# EPS_CTRL_AB_Supply.net
KiCad netlist of a schematic drawn in Altium Designer
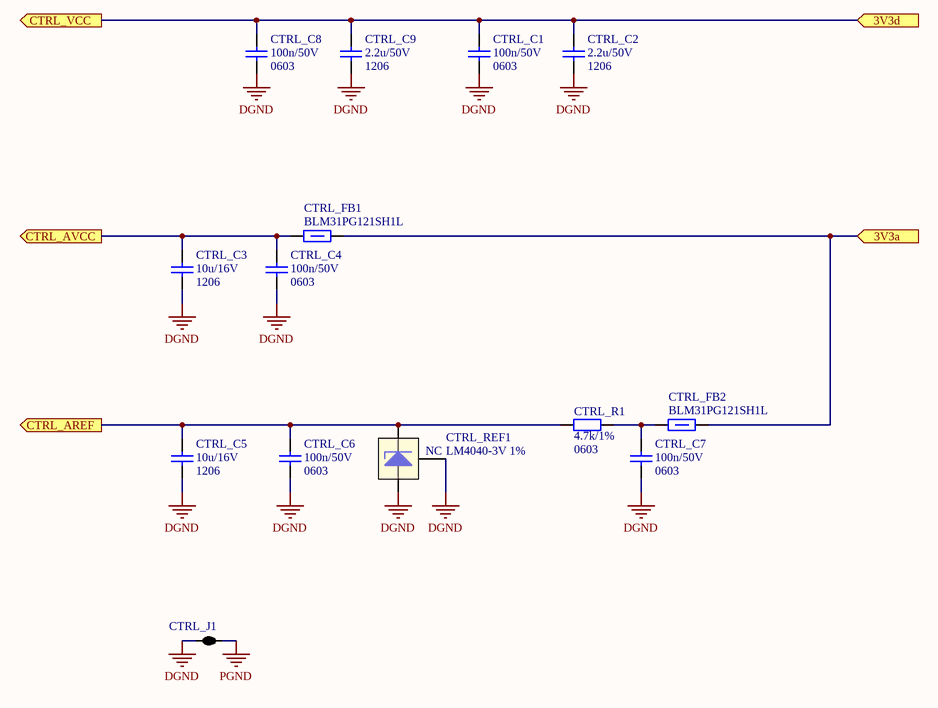
[diagram p0: EPS_CTRL_AB_Supply.SchDoc]

(export (version "E")
  (design (tool "Eeschema 10.0.6"))
  (components
    (comp (ref "CTRL_C1")
      (value "100n/50V")
      (footprint "SMD_Capacitor_0603")
      (description "Ceramic Cap Kemet COTS 100n/50V X7R 0603")
      (fields
        (field (name "MANUFACTURER") "Kemet")
        (field (name "MANUFACTURERPARTNUMBER") "C0603T104K5RALTU")
        (field (name "PACKAGE") "0603")
      )
      (libsource (lib "capacitors") (part "Cer_C0603T104K5RALTU"))
    )
    (comp (ref "CTRL_C2")
      (value "2.2u/50V")
      (footprint "SMD_Capacitor_1206")
      (description "Ceramic Cap Murata Automotive 2.2u/50V X7R 1206")
      (fields
        (field (name "MANUFACTURER") "Murata")
        (field (name "MANUFACTURERPARTNUMBER") "GCJ31CR71H225KA12L")
        (field (name "PACKAGE") "1206")
      )
      (libsource (lib "capacitors") (part "Cer_GCJ31CR71H225KA12L"))
    )
    (comp (ref "CTRL_C3")
      (value "10u/16V")
      (footprint "SMD_Capacitor_1206")
      (description "Ceramic Cap Kemet COTS 10u/16V X7R 1206")
      (fields
        (field (name "MANUFACTURERPARTNUMBER") "C1206T106K4RACTU")
        (field (name "MANUFACTURER") "Kemet")
        (field (name "PACKGE") "1206")
      )
      (libsource (lib "capacitors") (part "Cer_C1206T106K4RACTU"))
    )
    (comp (ref "CTRL_C4")
      (value "100n/50V")
      (footprint "SMD_Capacitor_0603")
      (description "Ceramic Cap Kemet COTS 100n/50V X7R 0603")
      (fields
        (field (name "MANUFACTURER") "Kemet")
        (field (name "MANUFACTURERPARTNUMBER") "C0603T104K5RALTU")
        (field (name "PACKAGE") "0603")
      )
      (libsource (lib "capacitors") (part "Cer_C0603T104K5RALTU"))
    )
    (comp (ref "CTRL_C5")
      (value "10u/16V")
      (footprint "SMD_Capacitor_1206")
      (description "Ceramic Cap Kemet COTS 10u/16V X7R 1206")
      (fields
        (field (name "MANUFACTURERPARTNUMBER") "C1206T106K4RACTU")
        (field (name "MANUFACTURER") "Kemet")
        (field (name "PACKGE") "1206")
      )
      (libsource (lib "capacitors") (part "Cer_C1206T106K4RACTU"))
    )
    (comp (ref "CTRL_C6")
      (value "100n/50V")
      (footprint "SMD_Capacitor_0603")
      (description "Ceramic Cap Kemet COTS 100n/50V X7R 0603")
      (fields
        (field (name "MANUFACTURER") "Kemet")
        (field (name "MANUFACTURERPARTNUMBER") "C0603T104K5RALTU")
        (field (name "PACKAGE") "0603")
      )
      (libsource (lib "capacitors") (part "Cer_C0603T104K5RALTU"))
    )
    (comp (ref "CTRL_C7")
      (value "100n/50V")
      (footprint "SMD_Capacitor_0603")
      (description "Ceramic Cap Kemet COTS 100n/50V X7R 0603")
      (fields
        (field (name "MANUFACTURER") "Kemet")
        (field (name "MANUFACTURERPARTNUMBER") "C0603T104K5RALTU")
        (field (name "PACKAGE") "0603")
      )
      (libsource (lib "capacitors") (part "Cer_C0603T104K5RALTU"))
    )
    (comp (ref "CTRL_C8")
      (value "100n/50V")
      (footprint "SMD_Capacitor_0603")
      (description "Ceramic Cap Kemet COTS 100n/50V X7R 0603")
      (fields
        (field (name "MANUFACTURER") "Kemet")
        (field (name "MANUFACTURERPARTNUMBER") "C0603T104K5RALTU")
        (field (name "PACKAGE") "0603")
      )
      (libsource (lib "capacitors") (part "Cer_C0603T104K5RALTU"))
    )
    (comp (ref "CTRL_C9")
      (value "2.2u/50V")
      (footprint "SMD_Capacitor_1206")
      (description "Ceramic Cap Murata Automotive 2.2u/50V X7R 1206")
      (fields
        (field (name "MANUFACTURER") "Murata")
        (field (name "MANUFACTURERPARTNUMBER") "GCJ31CR71H225KA12L")
        (field (name "PACKAGE") "1206")
      )
      (libsource (lib "capacitors") (part "Cer_GCJ31CR71H225KA12L"))
    )
    (comp (ref "CTRL_FB1")
      (value "120R/100MHz")
      (footprint "SMD_FerriteBead_1206")
      (description "Ferrite bead, 1206, 0.02HM, 3.5A.")
      (fields (field (name "MANUFACTURER") "Murata") (field (name "MANUFACTURERPARTNUMBER") "BLM31PG121SH1L"))
      (libsource (lib "inductors") (part "BLM31PG121SH1L"))
    )
    (comp (ref "CTRL_FB2")
      (value "120R/100MHz")
      (footprint "SMD_FerriteBead_1206")
      (description "Ferrite bead, 1206, 0.02HM, 3.5A.")
      (fields (field (name "MANUFACTURER") "Murata") (field (name "MANUFACTURERPARTNUMBER") "BLM31PG121SH1L"))
      (libsource (lib "inductors") (part "BLM31PG121SH1L"))
    )
    (comp (ref "CTRL_J1")
      (value "2 way net tie junction")
      (footprint "2way_LP")
      (libsource (lib "NetTieLib") (part "2way"))
    )
    (comp (ref "CTRL_R1")
      (value "4.7k/1%")
      (footprint "SMD_Resistor_0603")
      (fields (field (name "PACKAGE") "0603"))
      (libsource (lib "resistors") (part "Res"))
    )
    (comp (ref "CTRL_REF1")
      (value "LM4040-3V 1%")
      (footprint "SOT23-3")
      (description "Shunt V-REF, 3V, 1%, SOT23-3")
      (fields
        (field (name "MANUFACTURERPARTNUMBER") "LM4040DIM3-3.0")
        (field (name "MANUFACTURER") "Texas Instruments")
      )
      (libsource (lib "diodes") (part "LM4040DIM3-3.0"))
    )
  )
  (nets
    (net (code "1") (name "/3V3a") (class "Default")
      (node (ref "CTRL_FB1") (pin "1") (pinfunction "1_1") (pintype "passive"))
      (node (ref "CTRL_FB2") (pin "1") (pinfunction "1_1") (pintype "passive"))
    )
    (net (code "2") (name "/3V3d") (class "Default")
      (node (ref "CTRL_C1") (pin "1") (pinfunction "1_1") (pintype "passive"))
      (node (ref "CTRL_C2") (pin "1") (pinfunction "1_1") (pintype "passive"))
      (node (ref "CTRL_C8") (pin "1") (pinfunction "1_1") (pintype "passive"))
      (node (ref "CTRL_C9") (pin "1") (pinfunction "1_1") (pintype "passive"))
    )
    (net (code "3") (name "/CTRL_AREF") (class "Default")
      (node (ref "CTRL_C5") (pin "1") (pinfunction "1_1") (pintype "passive"))
      (node (ref "CTRL_C6") (pin "1") (pinfunction "1_1") (pintype "passive"))
      (node (ref "CTRL_R1") (pin "1") (pinfunction "1_1") (pintype "passive"))
      (node (ref "CTRL_REF1") (pin "1") (pinfunction "K_1") (pintype "passive"))
    )
    (net (code "4") (name "/CTRL_AVCC") (class "Default")
      (node (ref "CTRL_C3") (pin "1") (pinfunction "1_1") (pintype "passive"))
      (node (ref "CTRL_C4") (pin "1") (pinfunction "1_1") (pintype "passive"))
      (node (ref "CTRL_FB1") (pin "2") (pinfunction "2_2") (pintype "passive"))
    )
    (net (code "5") (name "DGND") (class "Default")
      (node (ref "CTRL_C1") (pin "2") (pinfunction "2_2") (pintype "passive"))
      (node (ref "CTRL_C2") (pin "2") (pinfunction "2_2") (pintype "passive"))
      (node (ref "CTRL_C3") (pin "2") (pinfunction "2_2") (pintype "passive"))
      (node (ref "CTRL_C4") (pin "2") (pinfunction "2_2") (pintype "passive"))
      (node (ref "CTRL_C5") (pin "2") (pinfunction "2_2") (pintype "passive"))
      (node (ref "CTRL_C6") (pin "2") (pinfunction "2_2") (pintype "passive"))
      (node (ref "CTRL_C7") (pin "2") (pinfunction "2_2") (pintype "passive"))
      (node (ref "CTRL_C8") (pin "2") (pinfunction "2_2") (pintype "passive"))
      (node (ref "CTRL_C9") (pin "2") (pinfunction "2_2") (pintype "passive"))
      (node (ref "CTRL_J1") (pin "2") (pinfunction "2_2") (pintype "passive"))
      (node (ref "CTRL_REF1") (pin "2") (pinfunction "A_2") (pintype "passive"))
      (node (ref "CTRL_REF1") (pin "3") (pinfunction "NC_3") (pintype "passive"))
    )
    (net (code "6") (name "Net-(CTRL_C7-Pad1)") (class "Default")
      (node (ref "CTRL_C7") (pin "1") (pinfunction "1_1") (pintype "passive"))
      (node (ref "CTRL_FB2") (pin "2") (pinfunction "2_2") (pintype "passive"))
      (node (ref "CTRL_R1") (pin "2") (pinfunction "2_2") (pintype "passive"))
    )
    (net (code "7") (name "PGND") (class "Default")
      (node (ref "CTRL_J1") (pin "1") (pinfunction "1_1") (pintype "passive"))
    )
  )
)
